# SmartDriveTestStand_SingleCape_v3.net
KiCad netlist of a schematic drawn in EAGLE
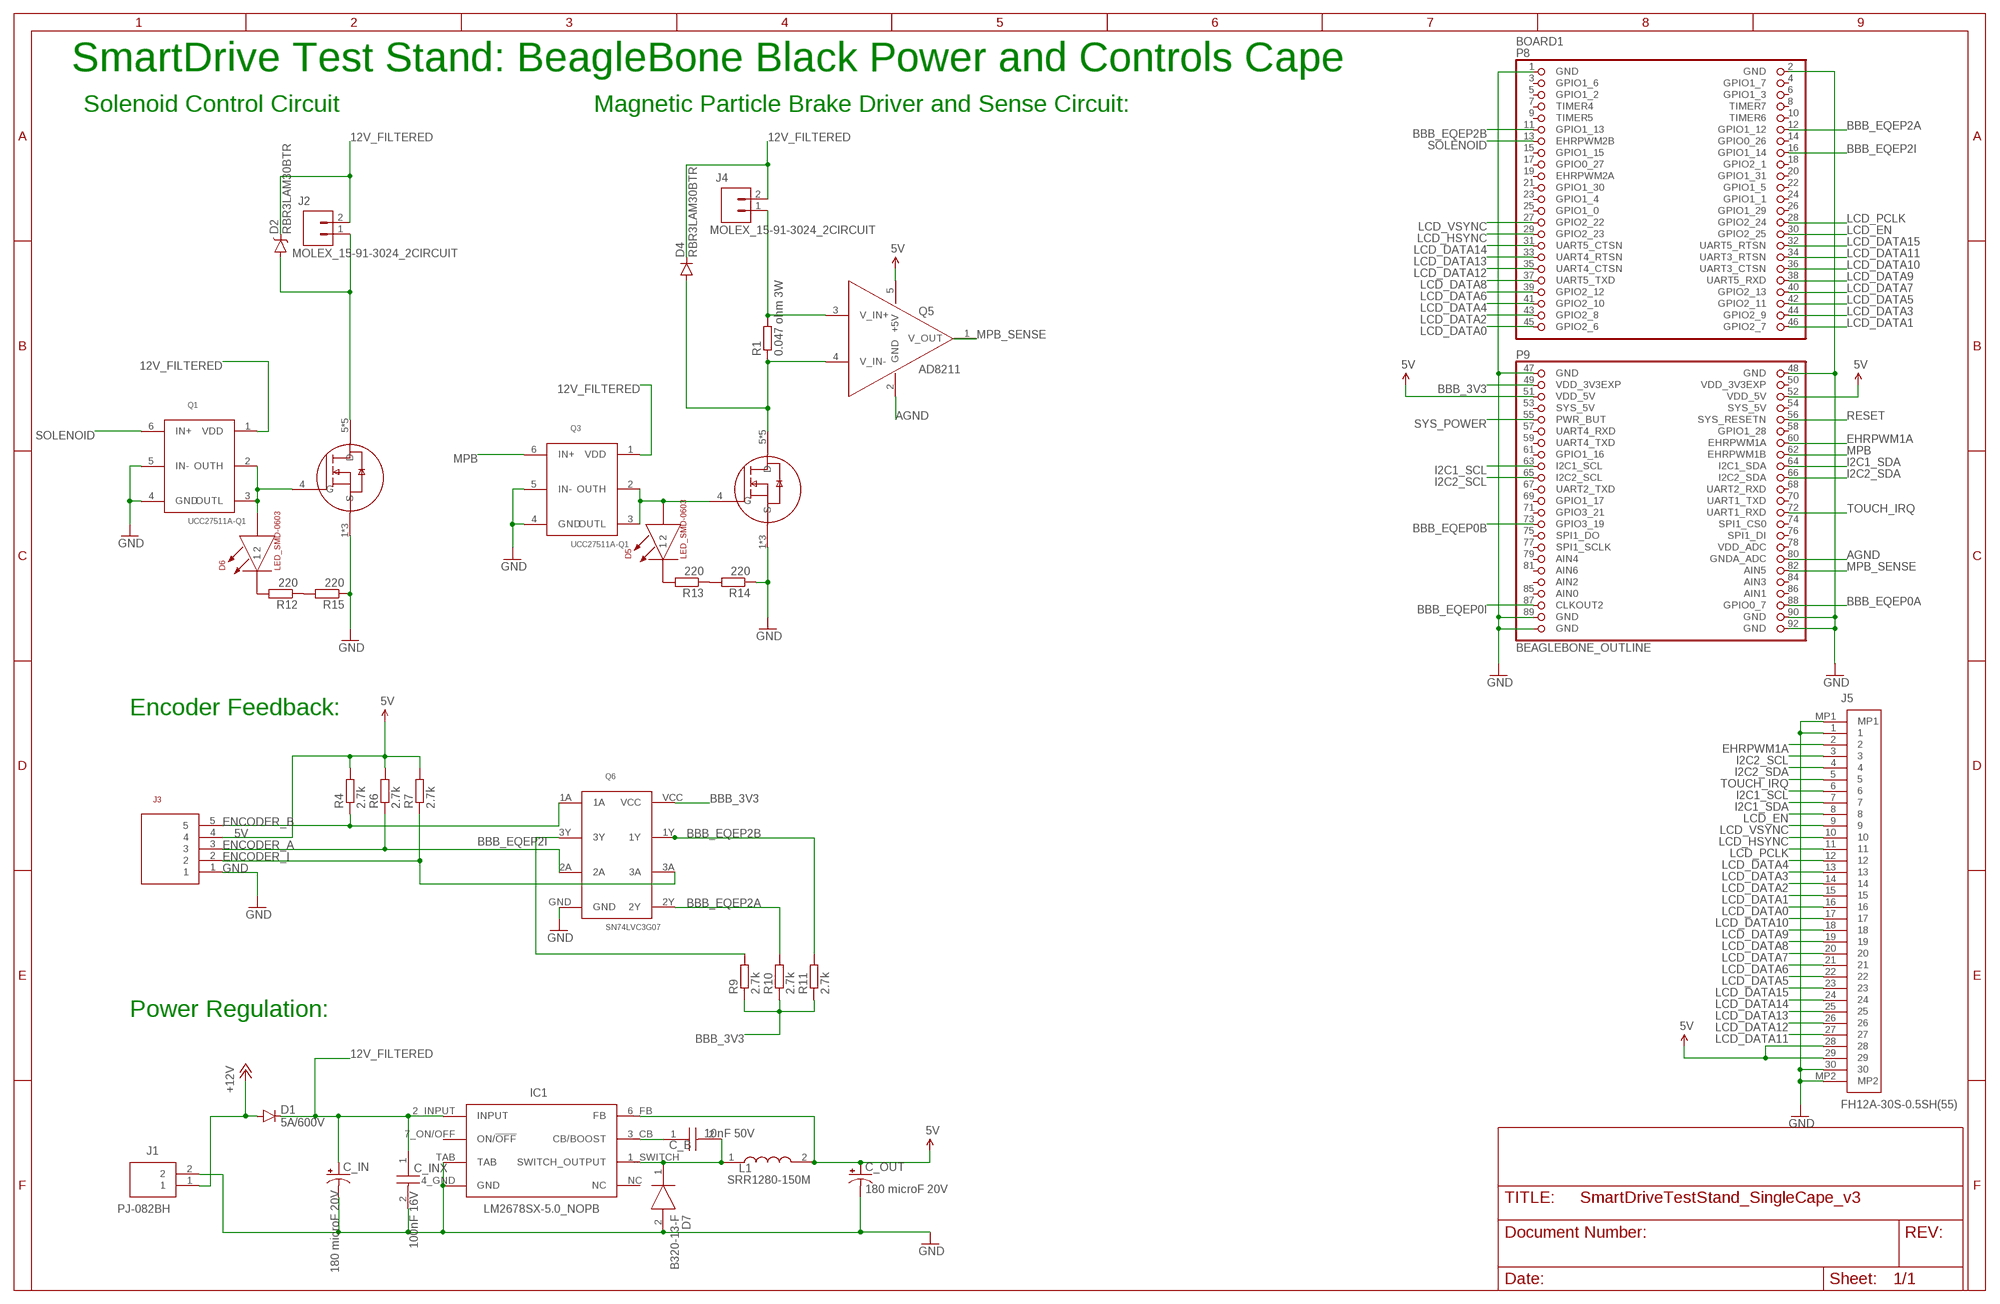
[diagram p0: schematic, sheet 1]

(export (version "E")
  (design (tool "Eeschema 10.0.6"))
  (components
    (comp (ref "BOARD1")
      (value "BEAGLEBONE_OUTLINE")
      (footprint "eagle-import:BEAGLEBONE_SHIELD")
      (libsource (lib "eagle-import") (part "BEAGLEBONE_OUTLINE"))
    )
    (comp (ref "C_B")
      (value "10nF 50V")
      (footprint "eagle-import:CAPC2012X75N")
      (fields
        (field (name "MANUFACTURER_PART_NUMBER") "CGA4C2C0G1H103J060AA")
        (field (name "MOUSER_PART_NUMBER") "810-CGA4C2C0G1H103J")
      )
      (libsource (lib "eagle-import") (part "CGA4C2C0G1H103J060AA"))
    )
    (comp (ref "C_IN")
      (value "180 microF 20V")
      (footprint "eagle-import:CAPAE1030X800N")
      (fields
        (field (name "MANUFACTURER_PART_NUMBER") "20SVPF180M")
        (field (name "MOUSER_PART_NUMBER") "667-20SVPF180M")
      )
      (libsource (lib "eagle-import") (part "20SVPF180M"))
    )
    (comp (ref "C_INX")
      (value "100nF 16V")
      (footprint "eagle-import:CAPC1608X90N")
      (fields
        (field (name "MANUFACTURER_PART_NUMBER") "C0603X104K4RACTU")
        (field (name "MOUSER_PART_NUMBER") "80-C0603X104K4R")
      )
      (libsource (lib "eagle-import") (part "C0603X104K4RACTU"))
    )
    (comp (ref "C_OUT")
      (value "180 microF 20V")
      (footprint "eagle-import:CAPAE1030X800N")
      (fields
        (field (name "MANUFACTURER_PART_NUMBER") "20SVPF180M")
        (field (name "MOUSER_PART_NUMBER") "667-20SVPF180M")
      )
      (libsource (lib "eagle-import") (part "20SVPF180M"))
    )
    (comp (ref "D1")
      (value "5A/600V")
      (footprint "eagle-import:SMC")
      (libsource (lib "eagle-import") (part "DIODEES3J"))
    )
    (comp (ref "D2")
      (value "RBR3LAM30BTR")
      (footprint "eagle-import:SMA-DIODE")
      (libsource (lib "eagle-import") (part "DIODE-SCHOTTKYRBR3LAM30B"))
    )
    (comp (ref "D4")
      (value "RBR3LAM30BTR")
      (footprint "eagle-import:SMA-DIODE")
      (libsource (lib "eagle-import") (part "DIODESMA"))
    )
    (comp (ref "D5")
      (value "LED_SMD-0603")
      (footprint "eagle-import:0603_LED")
      (libsource (lib "eagle-import") (part "LED_SMD-0603"))
    )
    (comp (ref "D6")
      (value "LED_SMD-0603")
      (footprint "eagle-import:0603_LED")
      (libsource (lib "eagle-import") (part "LED_SMD-0603"))
    )
    (comp (ref "D7")
      (value "B320-13-F")
      (footprint "eagle-import:DIOM7959X250N")
      (fields (field (name "MOUSER_PART_NUMBER") "621-B320-F"))
      (libsource (lib "eagle-import") (part "B320-13-F"))
    )
    (comp (ref "IC1")
      (value "LM2678SX-5.0_NOPB")
      (footprint "eagle-import:KTW0007B")
      (fields
        (field (name "MANUFACTURER_PART_NUMBER") "LM2678SX-5.0/NOPB")
        (field (name "MOUSER_PART_NUMBER") "926-LM2678SX50NOPB")
      )
      (libsource (lib "eagle-import") (part "LM2678SX-5.0_NOPB"))
    )
    (comp (ref "J1")
      (value "PJ-082BH")
      (footprint "eagle-import:PJ-082BH")
      (fields (field (name "MOUSER_PART_NUMBER") "490-PJ-082BH"))
      (libsource (lib "eagle-import") (part "PJ-082BH"))
    )
    (comp (ref "J2")
      (value "MOLEX_15-91-3024_2CIRCUIT")
      (footprint "eagle-import:MOLEX15-91-3024_2CIRCUIT")
      (libsource (lib "eagle-import") (part "MOLEX_15-91-3024_2CIRCUIT"))
    )
    (comp (ref "J3")
      (value "MOLEX_15-91-3053_5CIRCUIT")
      (footprint "eagle-import:MOLEX15-91-3053-5CIRCUIT")
      (libsource (lib "eagle-import") (part "MOLEX_15-91-3053_5CIRCUIT"))
    )
    (comp (ref "J4")
      (value "MOLEX_15-91-3024_2CIRCUIT")
      (footprint "eagle-import:MOLEX15-91-3024_2CIRCUIT")
      (libsource (lib "eagle-import") (part "MOLEX_15-91-3024_2CIRCUIT"))
    )
    (comp (ref "J5")
      (value "FH12A-30S-0.5SH(55)")
      (footprint "eagle-import:FH12A30S05SH55")
      (fields (field (name "RS_PART_NUMBER") "7148083P"))
      (libsource (lib "eagle-import") (part "FH12A-30S-0.5SH(55)"))
    )
    (comp (ref "L1")
      (value "SRR1280-150M")
      (footprint "eagle-import:SRR1280-150M")
      (fields (field (name "MOUSER_PART_NUMBER") "652-SRR1280-150M"))
      (libsource (lib "eagle-import") (part "SRR1280-150M"))
    )
    (comp (ref "Q1")
      (value "UCC27511A-Q1")
      (footprint "eagle-import:SOT23-6")
      (libsource (lib "eagle-import") (part "UCC27511A-Q1"))
    )
    (comp (ref "Q2")
      (value "MOSFET_NCHANNELTI_CSD18533Q5A")
      (footprint "eagle-import:SON_5X6MM_NEXFET")
      (libsource (lib "eagle-import") (part "MOSFET_NCHANNELTI_CSD18533Q5A"))
    )
    (comp (ref "Q3")
      (value "UCC27511A-Q1")
      (footprint "eagle-import:SOT23-6")
      (libsource (lib "eagle-import") (part "UCC27511A-Q1"))
    )
    (comp (ref "Q4")
      (value "MOSFET_NCHANNELTI_CSD18533Q5A")
      (footprint "eagle-import:SON_5X6MM_NEXFET")
      (libsource (lib "eagle-import") (part "MOSFET_NCHANNELTI_CSD18533Q5A"))
    )
    (comp (ref "Q5")
      (value "AD8211")
      (footprint "eagle-import:SOT23-5")
      (libsource (lib "eagle-import") (part "AD8211"))
    )
    (comp (ref "Q6")
      (value "SN74LVC3G07")
      (footprint "eagle-import:SN74LVC3G07")
      (libsource (lib "eagle-import") (part "SN74LVC3G07"))
    )
    (comp (ref "R1")
      (value "0.047 ohm 3W")
      (footprint "eagle-import:RESISTOR-2512")
      (libsource (lib "eagle-import") (part "RESISTOR-2512"))
    )
    (comp (ref "R4")
      (value "2.7k")
      (footprint "eagle-import:RESISTOR-0603")
      (libsource (lib "eagle-import") (part "RESISTOR-0603"))
    )
    (comp (ref "R6")
      (value "2.7k")
      (footprint "eagle-import:RESISTOR-0603")
      (libsource (lib "eagle-import") (part "RESISTOR-0603"))
    )
    (comp (ref "R7")
      (value "2.7k")
      (footprint "eagle-import:RESISTOR-0603")
      (libsource (lib "eagle-import") (part "RESISTOR-0603"))
    )
    (comp (ref "R9")
      (value "2.7k")
      (footprint "eagle-import:RESISTOR-0603")
      (libsource (lib "eagle-import") (part "RESISTOR-0603"))
    )
    (comp (ref "R10")
      (value "2.7k")
      (footprint "eagle-import:RESISTOR-0603")
      (libsource (lib "eagle-import") (part "RESISTOR-0603"))
    )
    (comp (ref "R11")
      (value "2.7k")
      (footprint "eagle-import:RESISTOR-0603")
      (libsource (lib "eagle-import") (part "RESISTOR-0603"))
    )
    (comp (ref "R12")
      (value "220")
      (footprint "eagle-import:RESISTOR-0603")
      (libsource (lib "eagle-import") (part "RESISTOR-0603"))
    )
    (comp (ref "R13")
      (value "220")
      (footprint "eagle-import:RESISTOR-0603")
      (libsource (lib "eagle-import") (part "RESISTOR-0603"))
    )
    (comp (ref "R14")
      (value "220")
      (footprint "eagle-import:RESISTOR-0603")
      (libsource (lib "eagle-import") (part "RESISTOR-0603"))
    )
    (comp (ref "R15")
      (value "220")
      (footprint "eagle-import:RESISTOR-0603")
      (libsource (lib "eagle-import") (part "RESISTOR-0603"))
    )
  )
  (nets
    (net (code "1") (name "+12V") (class "Default")
      (node (ref "D1") (pin "A") (pinfunction "A_A") (pintype "passive"))
      (node (ref "J1") (pin "1") (pinfunction "1_1") (pintype "bidirectional"))
    )
    (net (code "2") (name "/12V_FILTERED") (class "Default")
      (node (ref "C_IN") (pin "1") (pinfunction "+_1") (pintype "passive"))
      (node (ref "C_INX") (pin "1") (pinfunction "1_1") (pintype "bidirectional"))
      (node (ref "D1") (pin "C") (pinfunction "C_C") (pintype "passive"))
      (node (ref "D2") (pin "C") (pinfunction "C_C") (pintype "passive"))
      (node (ref "D4") (pin "C") (pinfunction "C_C") (pintype "passive"))
      (node (ref "IC1") (pin "2_INPUT") (pinfunction "INPUT_2_INPUT") (pintype "input"))
      (node (ref "J2") (pin "2") (pinfunction "2_2") (pintype "passive"))
      (node (ref "J4") (pin "2") (pinfunction "2_2") (pintype "passive"))
      (node (ref "Q1") (pin "1") (pinfunction "VDD_1") (pintype "bidirectional"))
      (node (ref "Q3") (pin "1") (pinfunction "VDD_1") (pintype "bidirectional"))
    )
    (net (code "3") (name "/AGND") (class "Default")
      (node (ref "BOARD1") (pin "80") (pinfunction "GNDA_ADC_80") (pintype "passive"))
      (node (ref "Q5") (pin "2") (pinfunction "GND_2") (pintype "power_in"))
    )
    (net (code "4") (name "/AIN0") (class "Default")
      (node (ref "BOARD1") (pin "85") (pinfunction "AIN0_85") (pintype "power_in"))
    )
    (net (code "5") (name "/BBB_3V3") (class "Default")
      (node (ref "BOARD1") (pin "49") (pinfunction "VDD_3V3EXP_49") (pintype "power_in"))
      (node (ref "Q6") (pin "VCC") (pinfunction "VCC_VCC") (pintype "bidirectional"))
      (node (ref "R10") (pin "P$1") (pinfunction "1_P$1") (pintype "passive"))
      (node (ref "R11") (pin "P$1") (pinfunction "1_P$1") (pintype "passive"))
      (node (ref "R9") (pin "P$1") (pinfunction "1_P$1") (pintype "passive"))
    )
    (net (code "6") (name "/BBB_EQEP0A") (class "Default")
      (node (ref "BOARD1") (pin "88") (pinfunction "GPIO0_7_88") (pintype "passive"))
    )
    (net (code "7") (name "/BBB_EQEP0B") (class "Default")
      (node (ref "BOARD1") (pin "73") (pinfunction "GPIO3_19_73") (pintype "passive"))
    )
    (net (code "8") (name "/BBB_EQEP0I") (class "Default")
      (node (ref "BOARD1") (pin "87") (pinfunction "CLKOUT2_87") (pintype "input"))
    )
    (net (code "9") (name "/BBB_EQEP2A") (class "Default")
      (node (ref "BOARD1") (pin "12") (pinfunction "GPIO1_12_12") (pintype "passive"))
      (node (ref "Q6") (pin "2Y") (pinfunction "2Y_2Y") (pintype "bidirectional"))
      (node (ref "R10") (pin "P$2") (pinfunction "2_P$2") (pintype "passive"))
    )
    (net (code "10") (name "/BBB_EQEP2B") (class "Default")
      (node (ref "BOARD1") (pin "11") (pinfunction "GPIO1_13_11") (pintype "passive"))
      (node (ref "Q6") (pin "1Y") (pinfunction "1Y_1Y") (pintype "bidirectional"))
      (node (ref "R11") (pin "P$2") (pinfunction "2_P$2") (pintype "passive"))
    )
    (net (code "11") (name "/BBB_EQEP2I") (class "Default")
      (node (ref "BOARD1") (pin "16") (pinfunction "GPIO1_14_16") (pintype "passive"))
      (node (ref "Q6") (pin "3Y") (pinfunction "3Y_3Y") (pintype "bidirectional"))
      (node (ref "R9") (pin "P$2") (pinfunction "2_P$2") (pintype "passive"))
    )
    (net (code "12") (name "/EHRPWM1A") (class "Default")
      (node (ref "BOARD1") (pin "60") (pinfunction "EHRPWM1A_60") (pintype "passive"))
      (node (ref "J5") (pin "2") (pinfunction "2_2") (pintype "bidirectional"))
    )
    (net (code "13") (name "/ENCODER_A") (class "Default")
      (node (ref "J3") (pin "3") (pinfunction "3_3") (pintype "passive"))
      (node (ref "Q6") (pin "2A") (pinfunction "2A_2A") (pintype "bidirectional"))
      (node (ref "R6") (pin "P$1") (pinfunction "1_P$1") (pintype "passive"))
    )
    (net (code "14") (name "/ENCODER_B") (class "Default")
      (node (ref "J3") (pin "5") (pinfunction "5_5") (pintype "passive"))
      (node (ref "Q6") (pin "1A") (pinfunction "1A_1A") (pintype "bidirectional"))
      (node (ref "R4") (pin "P$1") (pinfunction "1_P$1") (pintype "passive"))
    )
    (net (code "15") (name "/ENCODER_I") (class "Default")
      (node (ref "J3") (pin "2") (pinfunction "2_2") (pintype "passive"))
      (node (ref "Q6") (pin "3A") (pinfunction "3A_3A") (pintype "bidirectional"))
      (node (ref "R7") (pin "P$1") (pinfunction "1_P$1") (pintype "passive"))
    )
    (net (code "16") (name "/I2C1_SCL") (class "Default")
      (node (ref "BOARD1") (pin "63") (pinfunction "I2C1_SCL_63") (pintype "passive"))
      (node (ref "J5") (pin "6") (pinfunction "6_6") (pintype "bidirectional"))
    )
    (net (code "17") (name "/I2C1_SDA") (class "Default")
      (node (ref "BOARD1") (pin "64") (pinfunction "I2C1_SDA_64") (pintype "passive"))
      (node (ref "J5") (pin "7") (pinfunction "7_7") (pintype "bidirectional"))
    )
    (net (code "18") (name "/I2C2_SCL") (class "Default")
      (node (ref "BOARD1") (pin "65") (pinfunction "I2C2_SCL_65") (pintype "passive"))
      (node (ref "J5") (pin "3") (pinfunction "3_3") (pintype "bidirectional"))
    )
    (net (code "19") (name "/I2C2_SDA") (class "Default")
      (node (ref "BOARD1") (pin "66") (pinfunction "I2C2_SDA_66") (pintype "passive"))
      (node (ref "J5") (pin "4") (pinfunction "4_4") (pintype "bidirectional"))
    )
    (net (code "20") (name "/LCD_DATA0") (class "Default")
      (node (ref "BOARD1") (pin "45") (pinfunction "GPIO2_6_45") (pintype "passive"))
      (node (ref "J5") (pin "16") (pinfunction "16_16") (pintype "bidirectional"))
    )
    (net (code "21") (name "/LCD_DATA1") (class "Default")
      (node (ref "BOARD1") (pin "46") (pinfunction "GPIO2_7_46") (pintype "passive"))
      (node (ref "J5") (pin "15") (pinfunction "15_15") (pintype "bidirectional"))
    )
    (net (code "22") (name "/LCD_DATA2") (class "Default")
      (node (ref "BOARD1") (pin "43") (pinfunction "GPIO2_8_43") (pintype "passive"))
      (node (ref "J5") (pin "14") (pinfunction "14_14") (pintype "bidirectional"))
    )
    (net (code "23") (name "/LCD_DATA3") (class "Default")
      (node (ref "BOARD1") (pin "44") (pinfunction "GPIO2_9_44") (pintype "passive"))
      (node (ref "J5") (pin "13") (pinfunction "13_13") (pintype "bidirectional"))
    )
    (net (code "24") (name "/LCD_DATA4") (class "Default")
      (node (ref "BOARD1") (pin "41") (pinfunction "GPIO2_10_41") (pintype "passive"))
      (node (ref "J5") (pin "12") (pinfunction "12_12") (pintype "bidirectional"))
    )
    (net (code "25") (name "/LCD_DATA5") (class "Default")
      (node (ref "BOARD1") (pin "42") (pinfunction "GPIO2_11_42") (pintype "passive"))
      (node (ref "J5") (pin "22") (pinfunction "22_22") (pintype "bidirectional"))
    )
    (net (code "26") (name "/LCD_DATA6") (class "Default")
      (node (ref "BOARD1") (pin "39") (pinfunction "GPIO2_12_39") (pintype "passive"))
      (node (ref "J5") (pin "21") (pinfunction "21_21") (pintype "bidirectional"))
    )
    (net (code "27") (name "/LCD_DATA7") (class "Default")
      (node (ref "BOARD1") (pin "40") (pinfunction "GPIO2_13_40") (pintype "passive"))
      (node (ref "J5") (pin "20") (pinfunction "20_20") (pintype "bidirectional"))
    )
    (net (code "28") (name "/LCD_DATA8") (class "Default")
      (node (ref "BOARD1") (pin "37") (pinfunction "UART5_TXD_37") (pintype "passive"))
      (node (ref "J5") (pin "19") (pinfunction "19_19") (pintype "bidirectional"))
    )
    (net (code "29") (name "/LCD_DATA9") (class "Default")
      (node (ref "BOARD1") (pin "38") (pinfunction "UART5_RXD_38") (pintype "passive"))
      (node (ref "J5") (pin "18") (pinfunction "18_18") (pintype "bidirectional"))
    )
    (net (code "30") (name "/LCD_DATA10") (class "Default")
      (node (ref "BOARD1") (pin "36") (pinfunction "UART3_CTSN_36") (pintype "passive"))
      (node (ref "J5") (pin "17") (pinfunction "17_17") (pintype "bidirectional"))
    )
    (net (code "31") (name "/LCD_DATA11") (class "Default")
      (node (ref "BOARD1") (pin "34") (pinfunction "UART3_RTSN_34") (pintype "passive"))
      (node (ref "J5") (pin "27") (pinfunction "27_27") (pintype "bidirectional"))
    )
    (net (code "32") (name "/LCD_DATA12") (class "Default")
      (node (ref "BOARD1") (pin "35") (pinfunction "UART4_CTSN_35") (pintype "passive"))
      (node (ref "J5") (pin "26") (pinfunction "26_26") (pintype "bidirectional"))
    )
    (net (code "33") (name "/LCD_DATA13") (class "Default")
      (node (ref "BOARD1") (pin "33") (pinfunction "UART4_RTSN_33") (pintype "passive"))
      (node (ref "J5") (pin "25") (pinfunction "25_25") (pintype "bidirectional"))
    )
    (net (code "34") (name "/LCD_DATA14") (class "Default")
      (node (ref "BOARD1") (pin "31") (pinfunction "UART5_CTSN_31") (pintype "passive"))
      (node (ref "J5") (pin "24") (pinfunction "24_24") (pintype "bidirectional"))
    )
    (net (code "35") (name "/LCD_DATA15") (class "Default")
      (node (ref "BOARD1") (pin "32") (pinfunction "UART5_RTSN_32") (pintype "passive"))
      (node (ref "J5") (pin "23") (pinfunction "23_23") (pintype "bidirectional"))
    )
    (net (code "36") (name "/LCD_EN") (class "Default")
      (node (ref "BOARD1") (pin "30") (pinfunction "GPIO2_25_30") (pintype "passive"))
      (node (ref "J5") (pin "8") (pinfunction "8_8") (pintype "bidirectional"))
    )
    (net (code "37") (name "/LCD_HSYNC") (class "Default")
      (node (ref "BOARD1") (pin "29") (pinfunction "GPIO2_23_29") (pintype "passive"))
      (node (ref "J5") (pin "10") (pinfunction "10_10") (pintype "bidirectional"))
    )
    (net (code "38") (name "/LCD_PCLK") (class "Default")
      (node (ref "BOARD1") (pin "28") (pinfunction "GPIO2_24_28") (pintype "passive"))
      (node (ref "J5") (pin "11") (pinfunction "11_11") (pintype "bidirectional"))
    )
    (net (code "39") (name "/LCD_VSYNC") (class "Default")
      (node (ref "BOARD1") (pin "27") (pinfunction "GPIO2_22_27") (pintype "passive"))
      (node (ref "J5") (pin "9") (pinfunction "9_9") (pintype "bidirectional"))
    )
    (net (code "40") (name "/MPB") (class "Default")
      (node (ref "BOARD1") (pin "62") (pinfunction "EHRPWM1B_62") (pintype "passive"))
      (node (ref "Q3") (pin "6") (pinfunction "IN+_6") (pintype "bidirectional"))
    )
    (net (code "41") (name "/MPB_SENSE") (class "Default")
      (node (ref "BOARD1") (pin "82") (pinfunction "AIN5_82") (pintype "passive"))
      (node (ref "Q5") (pin "1") (pinfunction "V_OUT_1") (pintype "output"))
    )
    (net (code "42") (name "/RESET") (class "Default")
      (node (ref "BOARD1") (pin "56") (pinfunction "SYS_RESETN_56") (pintype "passive"))
    )
    (net (code "43") (name "/SOLENOID") (class "Default")
      (node (ref "BOARD1") (pin "13") (pinfunction "EHRPWM2B_13") (pintype "passive"))
      (node (ref "Q1") (pin "6") (pinfunction "IN+_6") (pintype "bidirectional"))
    )
    (net (code "44") (name "/SYS_5V") (class "Default")
      (node (ref "BOARD1") (pin "53") (pinfunction "SYS_5V_53") (pintype "power_in"))
    )
    (net (code "45") (name "/SYS_POWER") (class "Default")
      (node (ref "BOARD1") (pin "55") (pinfunction "PWR_BUT_55") (pintype "passive"))
    )
    (net (code "46") (name "/TOUCH_IRQ") (class "Default")
      (node (ref "BOARD1") (pin "72") (pinfunction "UART1_RXD_72") (pintype "passive"))
      (node (ref "J5") (pin "5") (pinfunction "5_5") (pintype "bidirectional"))
    )
    (net (code "47") (name "/VDD_3V3EXP") (class "Default")
      (node (ref "BOARD1") (pin "50") (pinfunction "VDD_3V3EXP_50") (pintype "power_in"))
    )
    (net (code "48") (name "5V") (class "Default")
      (node (ref "BOARD1") (pin "51") (pinfunction "VDD_5V_51") (pintype "power_in"))
      (node (ref "BOARD1") (pin "52") (pinfunction "VDD_5V_52") (pintype "power_in"))
      (node (ref "C_OUT") (pin "1") (pinfunction "+_1") (pintype "passive"))
      (node (ref "IC1") (pin "6_FB") (pinfunction "FB_6_FB") (pintype "input"))
      (node (ref "J3") (pin "4") (pinfunction "4_4") (pintype "passive"))
      (node (ref "J5") (pin "28") (pinfunction "28_28") (pintype "bidirectional"))
      (node (ref "J5") (pin "29") (pinfunction "29_29") (pintype "bidirectional"))
      (node (ref "L1") (pin "2") (pinfunction "2_2") (pintype "bidirectional"))
      (node (ref "Q5") (pin "5") (pinfunction "+5V_5") (pintype "power_in"))
      (node (ref "R4") (pin "P$2") (pinfunction "2_P$2") (pintype "passive"))
      (node (ref "R6") (pin "P$2") (pinfunction "2_P$2") (pintype "passive"))
      (node (ref "R7") (pin "P$2") (pinfunction "2_P$2") (pintype "passive"))
    )
    (net (code "49") (name "GND") (class "Default")
      (node (ref "BOARD1") (pin "1") (pinfunction "GND_1") (pintype "power_in"))
      (node (ref "BOARD1") (pin "2") (pinfunction "GND_2") (pintype "power_in"))
      (node (ref "BOARD1") (pin "47") (pinfunction "GND_47") (pintype "power_in"))
      (node (ref "BOARD1") (pin "48") (pinfunction "GND_48") (pintype "power_in"))
      (node (ref "BOARD1") (pin "89") (pinfunction "GND_89") (pintype "power_in"))
      (node (ref "BOARD1") (pin "90") (pinfunction "GND_90") (pintype "power_in"))
      (node (ref "BOARD1") (pin "91") (pinfunction "GND_91") (pintype "power_in"))
      (node (ref "BOARD1") (pin "92") (pinfunction "GND_92") (pintype "power_in"))
      (node (ref "C_IN") (pin "2") (pinfunction "-_2") (pintype "passive"))
      (node (ref "C_INX") (pin "2") (pinfunction "2_2") (pintype "bidirectional"))
      (node (ref "C_OUT") (pin "2") (pinfunction "-_2") (pintype "passive"))
      (node (ref "D7") (pin "2") (pinfunction "A_2") (pintype "bidirectional"))
      (node (ref "IC1") (pin "4_GND") (pinfunction "GND_4_GND") (pintype "power_in"))
      (node (ref "IC1") (pin "TAB") (pinfunction "TAB_TAB") (pintype "power_in"))
      (node (ref "J1") (pin "2") (pinfunction "2_2") (pintype "bidirectional"))
      (node (ref "J3") (pin "1") (pinfunction "1_1") (pintype "passive"))
      (node (ref "J5") (pin "1") (pinfunction "1_1") (pintype "bidirectional"))
      (node (ref "J5") (pin "30") (pinfunction "30_30") (pintype "bidirectional"))
      (node (ref "J5") (pin "MP1") (pinfunction "MP1_MP1") (pintype "bidirectional"))
      (node (ref "J5") (pin "MP2") (pinfunction "MP2_MP2") (pintype "bidirectional"))
      (node (ref "Q1") (pin "4") (pinfunction "GND_4") (pintype "bidirectional"))
      (node (ref "Q1") (pin "5") (pinfunction "IN-_5") (pintype "bidirectional"))
      (node (ref "Q2") (pin "1") (pinfunction "S_1") (pintype "power_in"))
      (node (ref "Q2") (pin "2") (pinfunction "S_2") (pintype "power_in"))
      (node (ref "Q2") (pin "3") (pinfunction "S_3") (pintype "power_in"))
      (node (ref "Q3") (pin "4") (pinfunction "GND_4") (pintype "bidirectional"))
      (node (ref "Q3") (pin "5") (pinfunction "IN-_5") (pintype "bidirectional"))
      (node (ref "Q4") (pin "1") (pinfunction "S_1") (pintype "power_in"))
      (node (ref "Q4") (pin "2") (pinfunction "S_2") (pintype "power_in"))
      (node (ref "Q4") (pin "3") (pinfunction "S_3") (pintype "power_in"))
      (node (ref "Q6") (pin "GND") (pinfunction "GND_GND") (pintype "bidirectional"))
      (node (ref "R14") (pin "P$1") (pinfunction "1_P$1") (pintype "passive"))
      (node (ref "R15") (pin "P$1") (pinfunction "1_P$1") (pintype "passive"))
    )
    (net (code "50") (name "Net-(D2-PadA)") (class "Default")
      (node (ref "D2") (pin "A") (pinfunction "A_A") (pintype "passive"))
      (node (ref "J2") (pin "1") (pinfunction "1_1") (pintype "passive"))
      (node (ref "Q2") (pin "5") (pinfunction "D_5") (pintype "power_in"))
      (node (ref "Q2") (pin "6") (pinfunction "D_6") (pintype "power_in"))
      (node (ref "Q2") (pin "7") (pinfunction "D_7") (pintype "power_in"))
      (node (ref "Q2") (pin "8") (pinfunction "D_8") (pintype "power_in"))
      (node (ref "Q2") (pin "PAD") (pinfunction "D_PAD") (pintype "power_in"))
    )
    (net (code "51") (name "Net-(D5-1)") (class "Default")
      (node (ref "D5") (pin "C") (pinfunction "1_C") (pintype "output"))
      (node (ref "R13") (pin "P$2") (pinfunction "2_P$2") (pintype "passive"))
    )
    (net (code "52") (name "Net-(D5-2)") (class "Default")
      (node (ref "D5") (pin "A") (pinfunction "2_A") (pintype "input"))
      (node (ref "Q3") (pin "2") (pinfunction "OUTH_2") (pintype "bidirectional"))
      (node (ref "Q3") (pin "3") (pinfunction "OUTL_3") (pintype "bidirectional"))
      (node (ref "Q4") (pin "4") (pinfunction "G_4") (pintype "input"))
    )
    (net (code "53") (name "Net-(D6-1)") (class "Default")
      (node (ref "D6") (pin "C") (pinfunction "1_C") (pintype "output"))
      (node (ref "R12") (pin "P$2") (pinfunction "2_P$2") (pintype "passive"))
    )
    (net (code "54") (name "Net-(D6-2)") (class "Default")
      (node (ref "D6") (pin "A") (pinfunction "2_A") (pintype "input"))
      (node (ref "Q1") (pin "2") (pinfunction "OUTH_2") (pintype "bidirectional"))
      (node (ref "Q1") (pin "3") (pinfunction "OUTL_3") (pintype "bidirectional"))
      (node (ref "Q2") (pin "4") (pinfunction "G_4") (pintype "input"))
    )
    (net (code "55") (name "Net-(D7-K)") (class "Default")
      (node (ref "C_B") (pin "2") (pinfunction "2_2") (pintype "bidirectional"))
      (node (ref "D7") (pin "1") (pinfunction "K_1") (pintype "bidirectional"))
      (node (ref "IC1") (pin "1_SWITCH") (pinfunction "SWITCH_OUTPUT_1_SWITCH") (pintype "output"))
      (node (ref "L1") (pin "1") (pinfunction "1_1") (pintype "bidirectional"))
    )
    (net (code "56") (name "Net-(IC1-CB{slash}BOOST)") (class "Default")
      (node (ref "C_B") (pin "1") (pinfunction "1_1") (pintype "bidirectional"))
      (node (ref "IC1") (pin "3_CB") (pinfunction "CB/BOOST_3_CB") (pintype "input"))
    )
    (net (code "57") (name "Net-(Q5-V_IN+)") (class "Default")
      (node (ref "J4") (pin "1") (pinfunction "1_1") (pintype "passive"))
      (node (ref "Q5") (pin "3") (pinfunction "V_IN+_3") (pintype "input"))
      (node (ref "R1") (pin "2") (pinfunction "2_2") (pintype "passive"))
    )
    (net (code "58") (name "Net-(Q5-V_IN-)") (class "Default")
      (node (ref "D4") (pin "A") (pinfunction "A_A") (pintype "passive"))
      (node (ref "Q4") (pin "5") (pinfunction "D_5") (pintype "power_in"))
      (node (ref "Q4") (pin "6") (pinfunction "D_6") (pintype "power_in"))
      (node (ref "Q4") (pin "7") (pinfunction "D_7") (pintype "power_in"))
      (node (ref "Q4") (pin "8") (pinfunction "D_8") (pintype "power_in"))
      (node (ref "Q4") (pin "PAD") (pinfunction "D_PAD") (pintype "power_in"))
      (node (ref "Q5") (pin "4") (pinfunction "V_IN-_4") (pintype "input"))
      (node (ref "R1") (pin "1") (pinfunction "1_1") (pintype "passive"))
    )
    (net (code "59") (name "Net-(R12-1)") (class "Default")
      (node (ref "R12") (pin "P$1") (pinfunction "1_P$1") (pintype "passive"))
      (node (ref "R15") (pin "P$2") (pinfunction "2_P$2") (pintype "passive"))
    )
    (net (code "60") (name "Net-(R13-1)") (class "Default")
      (node (ref "R13") (pin "P$1") (pinfunction "1_P$1") (pintype "passive"))
      (node (ref "R14") (pin "P$2") (pinfunction "2_P$2") (pintype "passive"))
    )
    (net (code "61") (name "unconnected-(BOARD1-AIN1-Pad86)") (class "Default")
      (node (ref "BOARD1") (pin "86") (pinfunction "AIN1_86") (pintype "passive"))
    )
    (net (code "62") (name "unconnected-(BOARD1-AIN2-Pad83)") (class "Default")
      (node (ref "BOARD1") (pin "83") (pinfunction "AIN2_83") (pintype "passive"))
    )
    (net (code "63") (name "unconnected-(BOARD1-AIN3-Pad84)") (class "Default")
      (node (ref "BOARD1") (pin "84") (pinfunction "AIN3_84") (pintype "passive"))
    )
    (net (code "64") (name "unconnected-(BOARD1-AIN4-Pad79)") (class "Default")
      (node (ref "BOARD1") (pin "79") (pinfunction "AIN4_79") (pintype "passive"))
    )
    (net (code "65") (name "unconnected-(BOARD1-AIN6-Pad81)") (class "Default")
      (node (ref "BOARD1") (pin "81") (pinfunction "AIN6_81") (pintype "passive"))
    )
    (net (code "66") (name "unconnected-(BOARD1-EHRPWM2A-Pad19)") (class "Default")
      (node (ref "BOARD1") (pin "19") (pinfunction "EHRPWM2A_19") (pintype "passive"))
    )
    (net (code "67") (name "unconnected-(BOARD1-GPIO0_26-Pad14)") (class "Default")
      (node (ref "BOARD1") (pin "14") (pinfunction "GPIO0_26_14") (pintype "passive"))
    )
    (net (code "68") (name "unconnected-(BOARD1-GPIO0_27-Pad17)") (class "Default")
      (node (ref "BOARD1") (pin "17") (pinfunction "GPIO0_27_17") (pintype "passive"))
    )
    (net (code "69") (name "unconnected-(BOARD1-GPIO1_0-Pad25)") (class "Default")
      (node (ref "BOARD1") (pin "25") (pinfunction "GPIO1_0_25") (pintype "passive"))
    )
    (net (code "70") (name "unconnected-(BOARD1-GPIO1_1-Pad24)") (class "Default")
      (node (ref "BOARD1") (pin "24") (pinfunction "GPIO1_1_24") (pintype "passive"))
    )
    (net (code "71") (name "unconnected-(BOARD1-GPIO1_2-Pad5)") (class "Default")
      (node (ref "BOARD1") (pin "5") (pinfunction "GPIO1_2_5") (pintype "passive"))
    )
    (net (code "72") (name "unconnected-(BOARD1-GPIO1_3-Pad6)") (class "Default")
      (node (ref "BOARD1") (pin "6") (pinfunction "GPIO1_3_6") (pintype "passive"))
    )
    (net (code "73") (name "unconnected-(BOARD1-GPIO1_4-Pad23)") (class "Default")
      (node (ref "BOARD1") (pin "23") (pinfunction "GPIO1_4_23") (pintype "passive"))
    )
    (net (code "74") (name "unconnected-(BOARD1-GPIO1_5-Pad22)") (class "Default")
      (node (ref "BOARD1") (pin "22") (pinfunction "GPIO1_5_22") (pintype "passive"))
    )
    (net (code "75") (name "unconnected-(BOARD1-GPIO1_6-Pad3)") (class "Default")
      (node (ref "BOARD1") (pin "3") (pinfunction "GPIO1_6_3") (pintype "passive"))
    )
    (net (code "76") (name "unconnected-(BOARD1-GPIO1_7-Pad4)") (class "Default")
      (node (ref "BOARD1") (pin "4") (pinfunction "GPIO1_7_4") (pintype "passive"))
    )
    (net (code "77") (name "unconnected-(BOARD1-GPIO1_15-Pad15)") (class "Default")
      (node (ref "BOARD1") (pin "15") (pinfunction "GPIO1_15_15") (pintype "passive"))
    )
    (net (code "78") (name "unconnected-(BOARD1-GPIO1_16-Pad61)") (class "Default")
      (node (ref "BOARD1") (pin "61") (pinfunction "GPIO1_16_61") (pintype "passive"))
    )
    (net (code "79") (name "unconnected-(BOARD1-GPIO1_17-Pad69)") (class "Default")
      (node (ref "BOARD1") (pin "69") (pinfunction "GPIO1_17_69") (pintype "passive"))
    )
    (net (code "80") (name "unconnected-(BOARD1-GPIO1_28-Pad58)") (class "Default")
      (node (ref "BOARD1") (pin "58") (pinfunction "GPIO1_28_58") (pintype "passive"))
    )
    (net (code "81") (name "unconnected-(BOARD1-GPIO1_29-Pad26)") (class "Default")
      (node (ref "BOARD1") (pin "26") (pinfunction "GPIO1_29_26") (pintype "passive"))
    )
    (net (code "82") (name "unconnected-(BOARD1-GPIO1_30-Pad21)") (class "Default")
      (node (ref "BOARD1") (pin "21") (pinfunction "GPIO1_30_21") (pintype "passive"))
    )
    (net (code "83") (name "unconnected-(BOARD1-GPIO1_31-Pad20)") (class "Default")
      (node (ref "BOARD1") (pin "20") (pinfunction "GPIO1_31_20") (pintype "passive"))
    )
    (net (code "84") (name "unconnected-(BOARD1-GPIO2_1-Pad18)") (class "Default")
      (node (ref "BOARD1") (pin "18") (pinfunction "GPIO2_1_18") (pintype "passive"))
    )
    (net (code "85") (name "unconnected-(BOARD1-GPIO3_21-Pad71)") (class "Default")
      (node (ref "BOARD1") (pin "71") (pinfunction "GPIO3_21_71") (pintype "passive"))
    )
    (net (code "86") (name "unconnected-(BOARD1-SPI1_CS0-Pad74)") (class "Default")
      (node (ref "BOARD1") (pin "74") (pinfunction "SPI1_CS0_74") (pintype "passive"))
    )
    (net (code "87") (name "unconnected-(BOARD1-SPI1_DI-Pad76)") (class "Default")
      (node (ref "BOARD1") (pin "76") (pinfunction "SPI1_DI_76") (pintype "passive"))
    )
    (net (code "88") (name "unconnected-(BOARD1-SPI1_DO-Pad75)") (class "Default")
      (node (ref "BOARD1") (pin "75") (pinfunction "SPI1_DO_75") (pintype "passive"))
    )
    (net (code "89") (name "unconnected-(BOARD1-SPI1_SCLK-Pad77)") (class "Default")
      (node (ref "BOARD1") (pin "77") (pinfunction "SPI1_SCLK_77") (pintype "passive"))
    )
    (net (code "90") (name "unconnected-(BOARD1-SYS_5V-Pad54)") (class "Default")
      (node (ref "BOARD1") (pin "54") (pinfunction "SYS_5V_54") (pintype "passive"))
    )
    (net (code "91") (name "unconnected-(BOARD1-TIMER4-Pad7)") (class "Default")
      (node (ref "BOARD1") (pin "7") (pinfunction "TIMER4_7") (pintype "passive"))
    )
    (net (code "92") (name "unconnected-(BOARD1-TIMER5-Pad9)") (class "Default")
      (node (ref "BOARD1") (pin "9") (pinfunction "TIMER5_9") (pintype "passive"))
    )
    (net (code "93") (name "unconnected-(BOARD1-TIMER6-Pad10)") (class "Default")
      (node (ref "BOARD1") (pin "10") (pinfunction "TIMER6_10") (pintype "passive"))
    )
    (net (code "94") (name "unconnected-(BOARD1-TIMER7-Pad8)") (class "Default")
      (node (ref "BOARD1") (pin "8") (pinfunction "TIMER7_8") (pintype "passive"))
    )
    (net (code "95") (name "unconnected-(BOARD1-UART1_TXD-Pad70)") (class "Default")
      (node (ref "BOARD1") (pin "70") (pinfunction "UART1_TXD_70") (pintype "passive"))
    )
    (net (code "96") (name "unconnected-(BOARD1-UART2_RXD-Pad68)") (class "Default")
      (node (ref "BOARD1") (pin "68") (pinfunction "UART2_RXD_68") (pintype "passive"))
    )
    (net (code "97") (name "unconnected-(BOARD1-UART2_TXD-Pad67)") (class "Default")
      (node (ref "BOARD1") (pin "67") (pinfunction "UART2_TXD_67") (pintype "passive"))
    )
    (net (code "98") (name "unconnected-(BOARD1-UART4_RXD-Pad57)") (class "Default")
      (node (ref "BOARD1") (pin "57") (pinfunction "UART4_RXD_57") (pintype "passive"))
    )
    (net (code "99") (name "unconnected-(BOARD1-UART4_TXD-Pad59)") (class "Default")
      (node (ref "BOARD1") (pin "59") (pinfunction "UART4_TXD_59") (pintype "passive"))
    )
    (net (code "100") (name "unconnected-(BOARD1-VDD_ADC-Pad78)") (class "Default")
      (node (ref "BOARD1") (pin "78") (pinfunction "VDD_ADC_78") (pintype "passive"))
    )
    (net (code "101") (name "unconnected-(IC1-ON{slash}~{OFF}-Pad7_ON{slash}OFF)") (class "Default")
      (node (ref "IC1") (pin "7_ON/OFF") (pinfunction "ON/~{OFF}_7_ON/OFF") (pintype "no_connect"))
    )
    (net (code "102") (name "unconnected-(IC1-PadNC)") (class "Default")
      (node (ref "IC1") (pin "NC") (pinfunction "NC_NC") (pintype "no_connect"))
    )
  )
)
